# midi-switcher-smt-relay.net
KiCad netlist of a schematic drawn in EAGLE
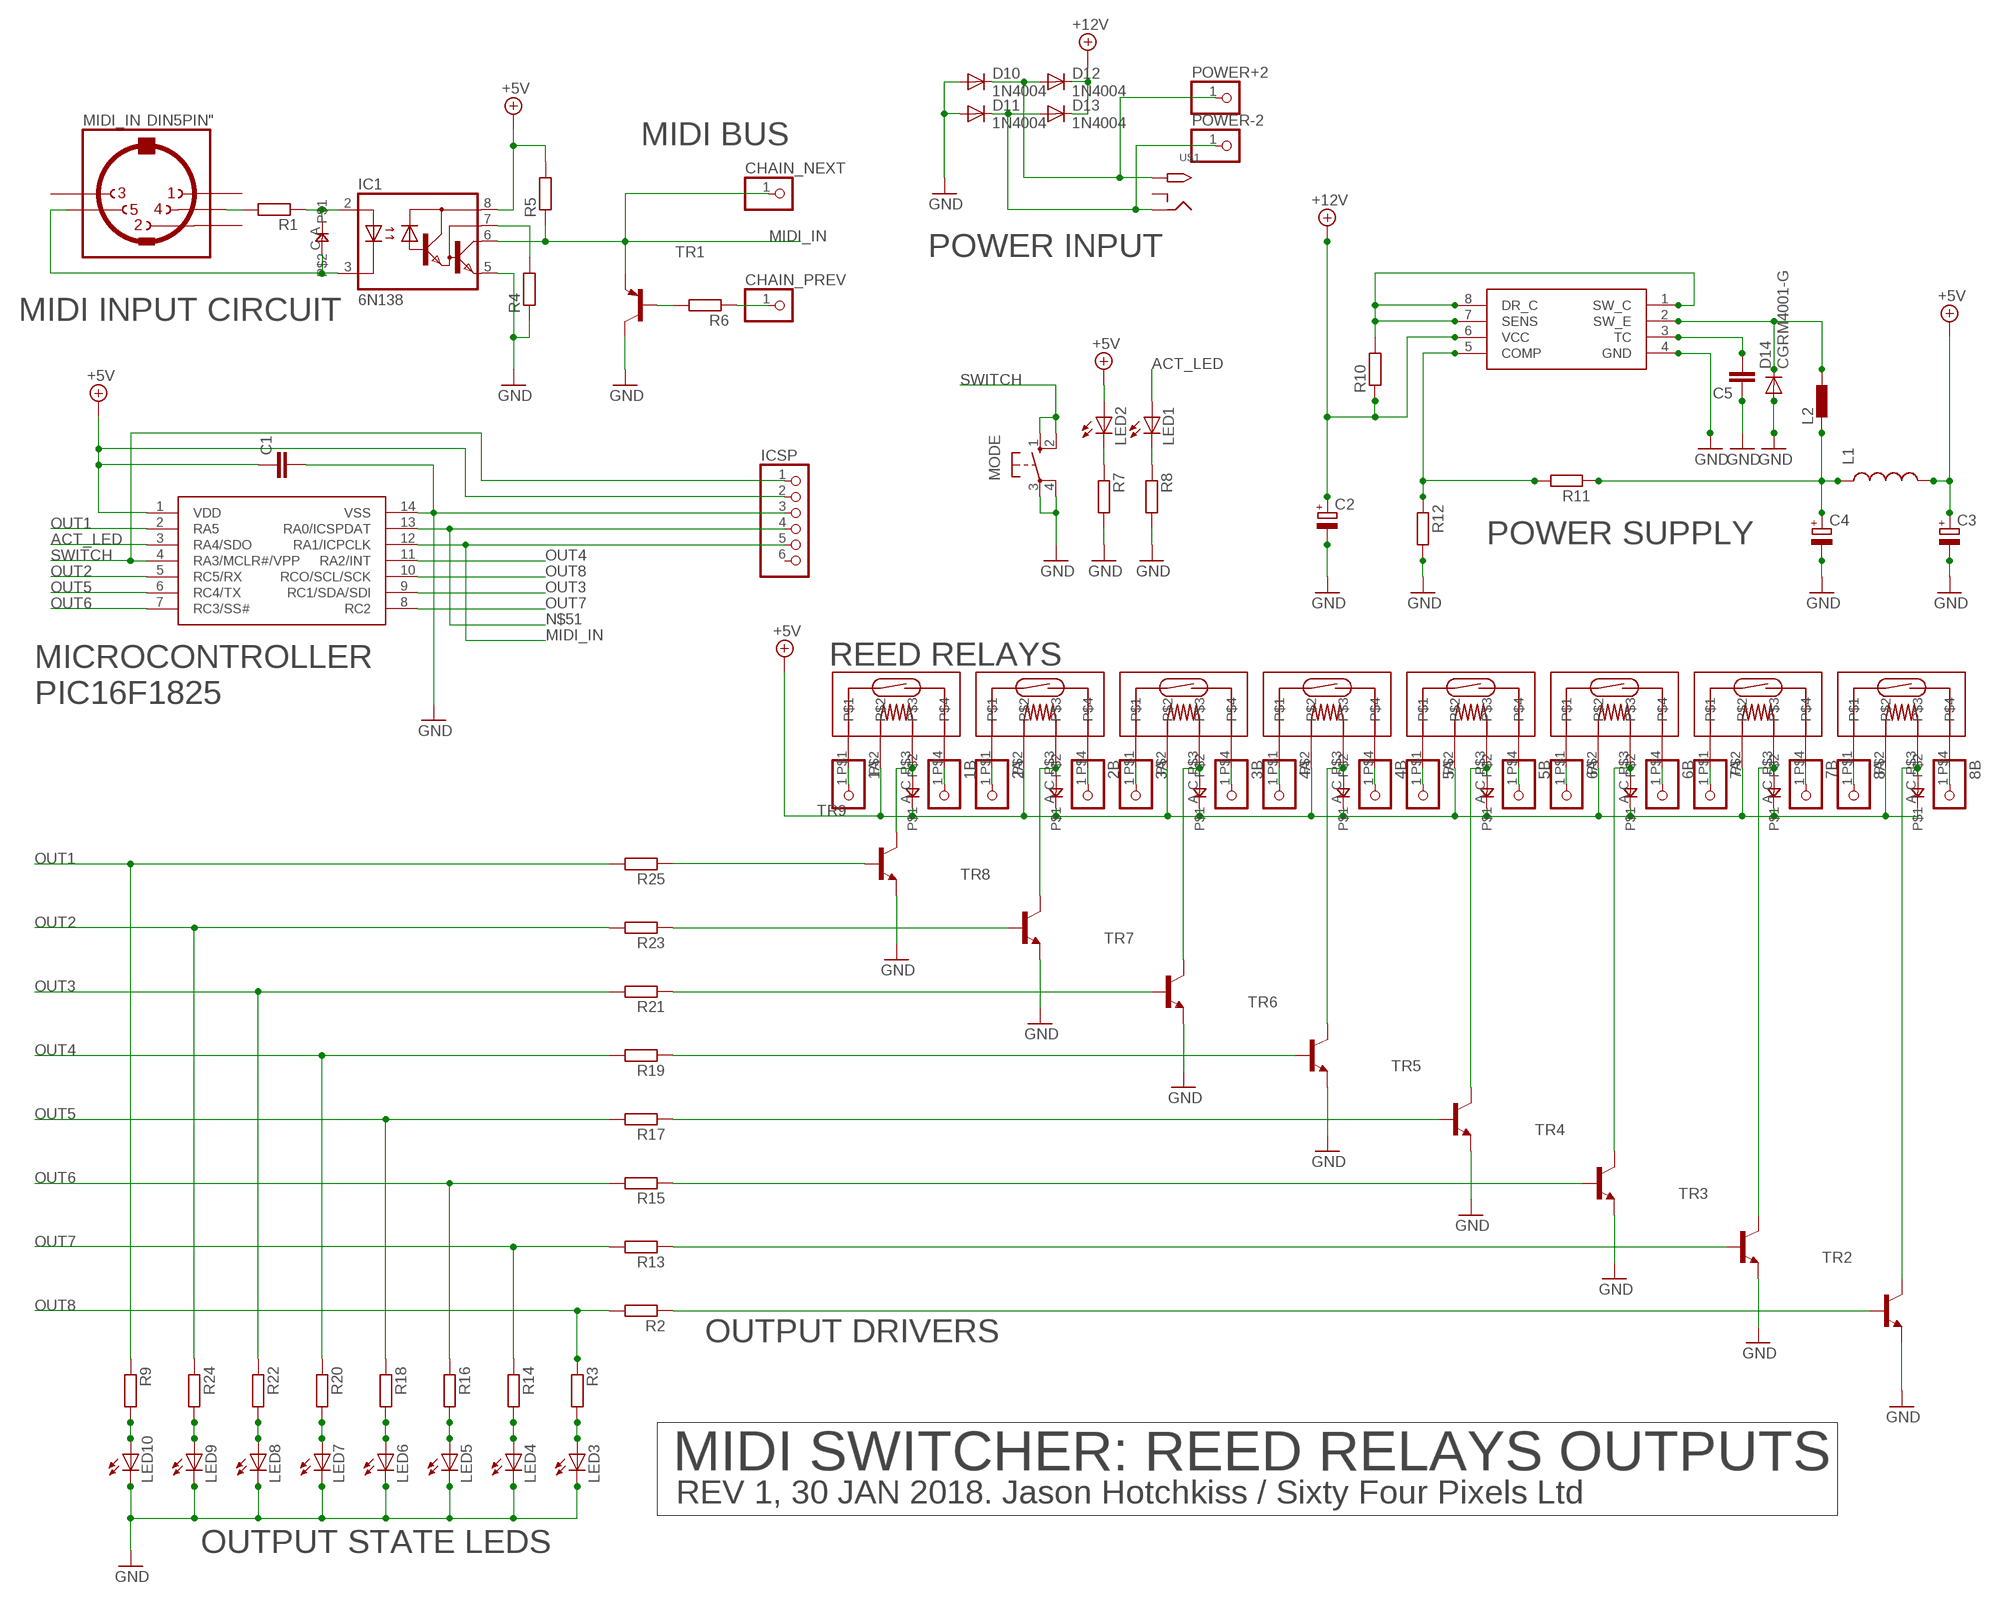
[diagram p0: schematic, sheet 1]

(export (version "E")
  (design (tool "Eeschema 10.0.6"))
  (components
    (comp (ref "1A")
      (value "PINHD-1X1")
      (footprint "eagle-import:1X01")
      (libsource (lib "eagle-import") (part "PINHD-1X1"))
    )
    (comp (ref "1B")
      (value "PINHD-1X1")
      (footprint "eagle-import:1X01")
      (libsource (lib "eagle-import") (part "PINHD-1X1"))
    )
    (comp (ref "2A")
      (value "PINHD-1X1")
      (footprint "eagle-import:1X01")
      (libsource (lib "eagle-import") (part "PINHD-1X1"))
    )
    (comp (ref "2B")
      (value "PINHD-1X1")
      (footprint "eagle-import:1X01")
      (libsource (lib "eagle-import") (part "PINHD-1X1"))
    )
    (comp (ref "3A")
      (value "PINHD-1X1")
      (footprint "eagle-import:1X01")
      (libsource (lib "eagle-import") (part "PINHD-1X1"))
    )
    (comp (ref "3B")
      (value "PINHD-1X1")
      (footprint "eagle-import:1X01")
      (libsource (lib "eagle-import") (part "PINHD-1X1"))
    )
    (comp (ref "4A")
      (value "PINHD-1X1")
      (footprint "eagle-import:1X01")
      (libsource (lib "eagle-import") (part "PINHD-1X1"))
    )
    (comp (ref "4B")
      (value "PINHD-1X1")
      (footprint "eagle-import:1X01")
      (libsource (lib "eagle-import") (part "PINHD-1X1"))
    )
    (comp (ref "5A")
      (value "PINHD-1X1")
      (footprint "eagle-import:1X01")
      (libsource (lib "eagle-import") (part "PINHD-1X1"))
    )
    (comp (ref "5B")
      (value "PINHD-1X1")
      (footprint "eagle-import:1X01")
      (libsource (lib "eagle-import") (part "PINHD-1X1"))
    )
    (comp (ref "6A")
      (value "PINHD-1X1")
      (footprint "eagle-import:1X01")
      (libsource (lib "eagle-import") (part "PINHD-1X1"))
    )
    (comp (ref "6B")
      (value "PINHD-1X1")
      (footprint "eagle-import:1X01")
      (libsource (lib "eagle-import") (part "PINHD-1X1"))
    )
    (comp (ref "7A")
      (value "PINHD-1X1")
      (footprint "eagle-import:1X01")
      (libsource (lib "eagle-import") (part "PINHD-1X1"))
    )
    (comp (ref "7B")
      (value "PINHD-1X1")
      (footprint "eagle-import:1X01")
      (libsource (lib "eagle-import") (part "PINHD-1X1"))
    )
    (comp (ref "8A")
      (value "PINHD-1X1")
      (footprint "eagle-import:1X01")
      (libsource (lib "eagle-import") (part "PINHD-1X1"))
    )
    (comp (ref "8B")
      (value "PINHD-1X1")
      (footprint "eagle-import:1X01")
      (libsource (lib "eagle-import") (part "PINHD-1X1"))
    )
    (comp (ref "C1")
      (value "C-EUC0805")
      (footprint "eagle-import:C0805")
      (libsource (lib "eagle-import") (part "C-EUC0805"))
    )
    (comp (ref "C2")
      (value "CPOL-EUE2.5-7")
      (footprint "eagle-import:E2,5-7")
      (libsource (lib "eagle-import") (part "CPOL-EUE2.5-7"))
    )
    (comp (ref "C3")
      (value "CPOL-EUE2.5-7")
      (footprint "eagle-import:E2,5-7")
      (libsource (lib "eagle-import") (part "CPOL-EUE2.5-7"))
    )
    (comp (ref "C4")
      (value "CPOL-EUE2.5-7")
      (footprint "eagle-import:E2,5-7")
      (libsource (lib "eagle-import") (part "CPOL-EUE2.5-7"))
    )
    (comp (ref "C5")
      (value "C-EUC0805")
      (footprint "eagle-import:C0805")
      (libsource (lib "eagle-import") (part "C-EUC0805"))
    )
    (comp (ref "CHAIN_NEXT")
      (value "PINHD-1X1")
      (footprint "eagle-import:1X01")
      (libsource (lib "eagle-import") (part "PINHD-1X1"))
    )
    (comp (ref "CHAIN_PREV")
      (value "PINHD-1X1")
      (footprint "eagle-import:1X01")
      (libsource (lib "eagle-import") (part "PINHD-1X1"))
    )
    (comp (ref "D1")
      (value "0805DIODE")
      (footprint "eagle-import:0805DIODE")
      (libsource (lib "eagle-import") (part "0805DIODE"))
    )
    (comp (ref "D2")
      (value "0805DIODE")
      (footprint "eagle-import:0805DIODE")
      (libsource (lib "eagle-import") (part "0805DIODE"))
    )
    (comp (ref "D3")
      (value "0805DIODE")
      (footprint "eagle-import:0805DIODE")
      (libsource (lib "eagle-import") (part "0805DIODE"))
    )
    (comp (ref "D4")
      (value "0805DIODE")
      (footprint "eagle-import:0805DIODE")
      (libsource (lib "eagle-import") (part "0805DIODE"))
    )
    (comp (ref "D5")
      (value "0805DIODE")
      (footprint "eagle-import:0805DIODE")
      (libsource (lib "eagle-import") (part "0805DIODE"))
    )
    (comp (ref "D6")
      (value "0805DIODE")
      (footprint "eagle-import:0805DIODE")
      (libsource (lib "eagle-import") (part "0805DIODE"))
    )
    (comp (ref "D7")
      (value "0805DIODE")
      (footprint "eagle-import:0805DIODE")
      (libsource (lib "eagle-import") (part "0805DIODE"))
    )
    (comp (ref "D8")
      (value "0805DIODE")
      (footprint "eagle-import:0805DIODE")
      (libsource (lib "eagle-import") (part "0805DIODE"))
    )
    (comp (ref "D9")
      (value "0805DIODE")
      (footprint "eagle-import:0805DIODE")
      (libsource (lib "eagle-import") (part "0805DIODE"))
    )
    (comp (ref "D10")
      (value "1N4004")
      (footprint "eagle-import:DO-VERT")
      (libsource (lib "eagle-import") (part "1N4004"))
    )
    (comp (ref "D11")
      (value "1N4004")
      (footprint "eagle-import:DO-VERT")
      (libsource (lib "eagle-import") (part "1N4004"))
    )
    (comp (ref "D12")
      (value "1N4004")
      (footprint "eagle-import:DO-VERT")
      (libsource (lib "eagle-import") (part "1N4004"))
    )
    (comp (ref "D13")
      (value "1N4004")
      (footprint "eagle-import:DO-VERT")
      (libsource (lib "eagle-import") (part "1N4004"))
    )
    (comp (ref "D14")
      (value "CGRM4001-G")
      (footprint "eagle-import:SOD-123_MINI-SMA")
      (libsource (lib "eagle-import") (part "CGRM400-G1"))
    )
    (comp (ref "IC1")
      (value "6N138")
      (footprint "eagle-import:DIL08")
      (libsource (lib "eagle-import") (part "6N138"))
    )
    (comp (ref "IC2")
      (value "PIC16F1825SO14")
      (footprint "eagle-import:SO14")
      (libsource (lib "eagle-import") (part "PIC16F1825SO14"))
    )
    (comp (ref "IC3")
      (value "SP34063A_BOOST_REG")
      (footprint "eagle-import:SOIC8")
      (libsource (lib "eagle-import") (part "SP34063A_BOOST_REG"))
    )
    (comp (ref "ICSP")
      (value "HEADER-1X6")
      (footprint "eagle-import:1X06_OVAL")
      (libsource (lib "eagle-import") (part "HEADER-1X6"))
    )
    (comp (ref "L1")
      (value "INDUCTOR1210")
      (footprint "eagle-import:1210")
      (libsource (lib "eagle-import") (part "INDUCTOR1210"))
    )
    (comp (ref "L2")
      (value "DR1030")
      (footprint "eagle-import:DR1030")
      (libsource (lib "eagle-import") (part "DR1030"))
    )
    (comp (ref "LED1")
      (value "LEDCHIP-LED0805")
      (footprint "eagle-import:CHIP-LED0805")
      (libsource (lib "eagle-import") (part "LEDCHIP-LED0805"))
    )
    (comp (ref "LED2")
      (value "LEDCHIP-LED0805")
      (footprint "eagle-import:CHIP-LED0805")
      (libsource (lib "eagle-import") (part "LEDCHIP-LED0805"))
    )
    (comp (ref "LED3")
      (value "LEDCHIP-LED0805")
      (footprint "eagle-import:CHIP-LED0805")
      (libsource (lib "eagle-import") (part "LEDCHIP-LED0805"))
    )
    (comp (ref "LED4")
      (value "LEDCHIP-LED0805")
      (footprint "eagle-import:CHIP-LED0805")
      (libsource (lib "eagle-import") (part "LEDCHIP-LED0805"))
    )
    (comp (ref "LED5")
      (value "LEDCHIP-LED0805")
      (footprint "eagle-import:CHIP-LED0805")
      (libsource (lib "eagle-import") (part "LEDCHIP-LED0805"))
    )
    (comp (ref "LED6")
      (value "LEDCHIP-LED0805")
      (footprint "eagle-import:CHIP-LED0805")
      (libsource (lib "eagle-import") (part "LEDCHIP-LED0805"))
    )
    (comp (ref "LED7")
      (value "LEDCHIP-LED0805")
      (footprint "eagle-import:CHIP-LED0805")
      (libsource (lib "eagle-import") (part "LEDCHIP-LED0805"))
    )
    (comp (ref "LED8")
      (value "LEDCHIP-LED0805")
      (footprint "eagle-import:CHIP-LED0805")
      (libsource (lib "eagle-import") (part "LEDCHIP-LED0805"))
    )
    (comp (ref "LED9")
      (value "LEDCHIP-LED0805")
      (footprint "eagle-import:CHIP-LED0805")
      (libsource (lib "eagle-import") (part "LEDCHIP-LED0805"))
    )
    (comp (ref "LED10")
      (value "LEDCHIP-LED0805")
      (footprint "eagle-import:CHIP-LED0805")
      (libsource (lib "eagle-import") (part "LEDCHIP-LED0805"))
    )
    (comp (ref "MIDI_IN")
      (value "DIN5PIN\"")
      (footprint "eagle-import:TRUCONN90")
      (libsource (lib "eagle-import") (part "DIN5PIN{dblquote}"))
    )
    (comp (ref "MODE")
      (value "10-XX")
      (footprint "eagle-import:B3F-10XX")
      (libsource (lib "eagle-import") (part "10-XX"))
    )
    (comp (ref "POWER+2")
      (value "PINHD-1X1")
      (footprint "eagle-import:1X01")
      (libsource (lib "eagle-import") (part "PINHD-1X1"))
    )
    (comp (ref "POWER-2")
      (value "PINHD-1X1")
      (footprint "eagle-import:1X01")
      (libsource (lib "eagle-import") (part "PINHD-1X1"))
    )
    (comp (ref "R1")
      (value "R-EU_R0805")
      (footprint "eagle-import:R0805")
      (libsource (lib "eagle-import") (part "R-EU_R0805"))
    )
    (comp (ref "R2")
      (value "R-EU_R0805")
      (footprint "eagle-import:R0805")
      (libsource (lib "eagle-import") (part "R-EU_R0805"))
    )
    (comp (ref "R3")
      (value "R-EU_R0805")
      (footprint "eagle-import:R0805")
      (libsource (lib "eagle-import") (part "R-EU_R0805"))
    )
    (comp (ref "R4")
      (value "R-EU_R0805")
      (footprint "eagle-import:R0805")
      (libsource (lib "eagle-import") (part "R-EU_R0805"))
    )
    (comp (ref "R5")
      (value "R-EU_R0805")
      (footprint "eagle-import:R0805")
      (libsource (lib "eagle-import") (part "R-EU_R0805"))
    )
    (comp (ref "R6")
      (value "R-EU_R0805")
      (footprint "eagle-import:R0805")
      (libsource (lib "eagle-import") (part "R-EU_R0805"))
    )
    (comp (ref "R7")
      (value "R-EU_R0805")
      (footprint "eagle-import:R0805")
      (libsource (lib "eagle-import") (part "R-EU_R0805"))
    )
    (comp (ref "R8")
      (value "R-EU_R0805")
      (footprint "eagle-import:R0805")
      (libsource (lib "eagle-import") (part "R-EU_R0805"))
    )
    (comp (ref "R9")
      (value "R-EU_R0805")
      (footprint "eagle-import:R0805")
      (libsource (lib "eagle-import") (part "R-EU_R0805"))
    )
    (comp (ref "R10")
      (value "R-EU_R0805")
      (footprint "eagle-import:R0805")
      (libsource (lib "eagle-import") (part "R-EU_R0805"))
    )
    (comp (ref "R11")
      (value "R-EU_R0805")
      (footprint "eagle-import:R0805")
      (libsource (lib "eagle-import") (part "R-EU_R0805"))
    )
    (comp (ref "R12")
      (value "R-EU_R0805")
      (footprint "eagle-import:R0805")
      (libsource (lib "eagle-import") (part "R-EU_R0805"))
    )
    (comp (ref "R13")
      (value "R-EU_R0805")
      (footprint "eagle-import:R0805")
      (libsource (lib "eagle-import") (part "R-EU_R0805"))
    )
    (comp (ref "R14")
      (value "R-EU_R0805")
      (footprint "eagle-import:R0805")
      (libsource (lib "eagle-import") (part "R-EU_R0805"))
    )
    (comp (ref "R15")
      (value "R-EU_R0805")
      (footprint "eagle-import:R0805")
      (libsource (lib "eagle-import") (part "R-EU_R0805"))
    )
    (comp (ref "R16")
      (value "R-EU_R0805")
      (footprint "eagle-import:R0805")
      (libsource (lib "eagle-import") (part "R-EU_R0805"))
    )
    (comp (ref "R17")
      (value "R-EU_R0805")
      (footprint "eagle-import:R0805")
      (libsource (lib "eagle-import") (part "R-EU_R0805"))
    )
    (comp (ref "R18")
      (value "R-EU_R0805")
      (footprint "eagle-import:R0805")
      (libsource (lib "eagle-import") (part "R-EU_R0805"))
    )
    (comp (ref "R19")
      (value "R-EU_R0805")
      (footprint "eagle-import:R0805")
      (libsource (lib "eagle-import") (part "R-EU_R0805"))
    )
    (comp (ref "R20")
      (value "R-EU_R0805")
      (footprint "eagle-import:R0805")
      (libsource (lib "eagle-import") (part "R-EU_R0805"))
    )
    (comp (ref "R21")
      (value "R-EU_R0805")
      (footprint "eagle-import:R0805")
      (libsource (lib "eagle-import") (part "R-EU_R0805"))
    )
    (comp (ref "R22")
      (value "R-EU_R0805")
      (footprint "eagle-import:R0805")
      (libsource (lib "eagle-import") (part "R-EU_R0805"))
    )
    (comp (ref "R23")
      (value "R-EU_R0805")
      (footprint "eagle-import:R0805")
      (libsource (lib "eagle-import") (part "R-EU_R0805"))
    )
    (comp (ref "R24")
      (value "R-EU_R0805")
      (footprint "eagle-import:R0805")
      (libsource (lib "eagle-import") (part "R-EU_R0805"))
    )
    (comp (ref "R25")
      (value "R-EU_R0805")
      (footprint "eagle-import:R0805")
      (libsource (lib "eagle-import") (part "R-EU_R0805"))
    )
    (comp (ref "RL1")
      (value "9007-REED-RELAY")
      (footprint "eagle-import:9007-REED-RELAY")
      (libsource (lib "eagle-import") (part "9007-REED-RELAY"))
    )
    (comp (ref "RL2")
      (value "9007-REED-RELAY")
      (footprint "eagle-import:9007-REED-RELAY")
      (libsource (lib "eagle-import") (part "9007-REED-RELAY"))
    )
    (comp (ref "RL3")
      (value "9007-REED-RELAY")
      (footprint "eagle-import:9007-REED-RELAY")
      (libsource (lib "eagle-import") (part "9007-REED-RELAY"))
    )
    (comp (ref "RL4")
      (value "9007-REED-RELAY")
      (footprint "eagle-import:9007-REED-RELAY")
      (libsource (lib "eagle-import") (part "9007-REED-RELAY"))
    )
    (comp (ref "RL5")
      (value "9007-REED-RELAY")
      (footprint "eagle-import:9007-REED-RELAY")
      (libsource (lib "eagle-import") (part "9007-REED-RELAY"))
    )
    (comp (ref "RL6")
      (value "9007-REED-RELAY")
      (footprint "eagle-import:9007-REED-RELAY")
      (libsource (lib "eagle-import") (part "9007-REED-RELAY"))
    )
    (comp (ref "RL7")
      (value "9007-REED-RELAY")
      (footprint "eagle-import:9007-REED-RELAY")
      (libsource (lib "eagle-import") (part "9007-REED-RELAY"))
    )
    (comp (ref "RL8")
      (value "9007-REED-RELAY")
      (footprint "eagle-import:9007-REED-RELAY")
      (libsource (lib "eagle-import") (part "9007-REED-RELAY"))
    )
    (comp (ref "TR1")
      (value "MMBT3906LT1-PNP-SOT23-BEC")
      (footprint "eagle-import:SOT23-BEC")
      (libsource (lib "eagle-import") (part "-PNP-SOT23-BECMMBT3906LT1"))
    )
    (comp (ref "TR2")
      (value "MMBT3904LT1-NPN-SOT23-BEC")
      (footprint "eagle-import:SOT23-BEC")
      (libsource (lib "eagle-import") (part "-NPN-SOT23-BECMMBT3904LT1"))
    )
    (comp (ref "TR3")
      (value "MMBT3904LT1-NPN-SOT23-BEC")
      (footprint "eagle-import:SOT23-BEC")
      (libsource (lib "eagle-import") (part "-NPN-SOT23-BECMMBT3904LT1"))
    )
    (comp (ref "TR4")
      (value "MMBT3904LT1-NPN-SOT23-BEC")
      (footprint "eagle-import:SOT23-BEC")
      (libsource (lib "eagle-import") (part "-NPN-SOT23-BECMMBT3904LT1"))
    )
    (comp (ref "TR5")
      (value "MMBT3904LT1-NPN-SOT23-BEC")
      (footprint "eagle-import:SOT23-BEC")
      (libsource (lib "eagle-import") (part "-NPN-SOT23-BECMMBT3904LT1"))
    )
    (comp (ref "TR6")
      (value "MMBT3904LT1-NPN-SOT23-BEC")
      (footprint "eagle-import:SOT23-BEC")
      (libsource (lib "eagle-import") (part "-NPN-SOT23-BECMMBT3904LT1"))
    )
    (comp (ref "TR7")
      (value "MMBT3904LT1-NPN-SOT23-BEC")
      (footprint "eagle-import:SOT23-BEC")
      (libsource (lib "eagle-import") (part "-NPN-SOT23-BECMMBT3904LT1"))
    )
    (comp (ref "TR8")
      (value "MMBT3904LT1-NPN-SOT23-BEC")
      (footprint "eagle-import:SOT23-BEC")
      (libsource (lib "eagle-import") (part "-NPN-SOT23-BECMMBT3904LT1"))
    )
    (comp (ref "TR9")
      (value "MMBT3904LT1-NPN-SOT23-BEC")
      (footprint "eagle-import:SOT23-BEC")
      (libsource (lib "eagle-import") (part "-NPN-SOT23-BECMMBT3904LT1"))
    )
    (comp (ref "U$1")
      (value "2.1MMJACKTHM")
      (footprint "eagle-import:PJ-102A")
      (libsource (lib "eagle-import") (part "2.1MMJACKTHM"))
    )
  )
  (nets
    (net (code "1") (name "+5V") (class "Default")
      (node (ref "C1") (pin "1") (pinfunction "1_1") (pintype "passive"))
      (node (ref "C3") (pin "+") (pinfunction "+_+") (pintype "passive"))
      (node (ref "D2") (pin "A") (pinfunction "P$2_A") (pintype "bidirectional"))
      (node (ref "D3") (pin "A") (pinfunction "P$2_A") (pintype "bidirectional"))
      (node (ref "D4") (pin "A") (pinfunction "P$2_A") (pintype "bidirectional"))
      (node (ref "D5") (pin "A") (pinfunction "P$2_A") (pintype "bidirectional"))
      (node (ref "D6") (pin "A") (pinfunction "P$2_A") (pintype "bidirectional"))
      (node (ref "D7") (pin "A") (pinfunction "P$2_A") (pintype "bidirectional"))
      (node (ref "D8") (pin "A") (pinfunction "P$2_A") (pintype "bidirectional"))
      (node (ref "D9") (pin "A") (pinfunction "P$2_A") (pintype "bidirectional"))
      (node (ref "IC1") (pin "8") (pinfunction "VCC_8") (pintype "passive"))
      (node (ref "IC2") (pin "1") (pinfunction "VDD_1") (pintype "power_in"))
      (node (ref "ICSP") (pin "2") (pinfunction "2_2") (pintype "passive"))
      (node (ref "L1") (pin "2") (pinfunction "2_2") (pintype "passive"))
      (node (ref "LED2") (pin "A") (pinfunction "A_A") (pintype "passive"))
      (node (ref "R5") (pin "2") (pinfunction "2_2") (pintype "passive"))
      (node (ref "RL1") (pin "P$2") (pinfunction "P$2_P$2") (pintype "bidirectional"))
      (node (ref "RL2") (pin "P$2") (pinfunction "P$2_P$2") (pintype "bidirectional"))
      (node (ref "RL3") (pin "P$2") (pinfunction "P$2_P$2") (pintype "bidirectional"))
      (node (ref "RL4") (pin "P$2") (pinfunction "P$2_P$2") (pintype "bidirectional"))
      (node (ref "RL5") (pin "P$2") (pinfunction "P$2_P$2") (pintype "bidirectional"))
      (node (ref "RL6") (pin "P$2") (pinfunction "P$2_P$2") (pintype "bidirectional"))
      (node (ref "RL7") (pin "P$2") (pinfunction "P$2_P$2") (pintype "bidirectional"))
      (node (ref "RL8") (pin "P$2") (pinfunction "P$2_P$2") (pintype "bidirectional"))
    )
    (net (code "2") (name "+12V") (class "Default")
      (node (ref "C2") (pin "+") (pinfunction "+_+") (pintype "passive"))
      (node (ref "D12") (pin "C") (pinfunction "C_C") (pintype "passive"))
      (node (ref "D13") (pin "C") (pinfunction "C_C") (pintype "passive"))
      (node (ref "IC3") (pin "6") (pinfunction "VCC_6") (pintype "bidirectional"))
      (node (ref "R10") (pin "1") (pinfunction "1_1") (pintype "passive"))
    )
    (net (code "3") (name "/ACT_LED") (class "Default")
      (node (ref "IC2") (pin "3") (pinfunction "RA4/SDO_3") (pintype "bidirectional"))
      (node (ref "LED1") (pin "A") (pinfunction "A_A") (pintype "passive"))
    )
    (net (code "4") (name "/MIDI_IN") (class "Default")
      (node (ref "CHAIN_NEXT") (pin "1") (pinfunction "1_1") (pintype "passive"))
      (node (ref "IC1") (pin "6") (pinfunction "VO_6") (pintype "passive"))
      (node (ref "IC2") (pin "12") (pinfunction "RA1/ICPCLK_12") (pintype "bidirectional"))
      (node (ref "ICSP") (pin "5") (pinfunction "5_5") (pintype "passive"))
      (node (ref "R5") (pin "1") (pinfunction "1_1") (pintype "passive"))
      (node (ref "TR1") (pin "E") (pinfunction "E_E") (pintype "passive"))
    )
    (net (code "5") (name "/N$51") (class "Default")
      (node (ref "IC2") (pin "13") (pinfunction "RA0/ICSPDAT_13") (pintype "bidirectional"))
      (node (ref "ICSP") (pin "4") (pinfunction "4_4") (pintype "passive"))
    )
    (net (code "6") (name "/OUT1") (class "Default")
      (node (ref "IC2") (pin "2") (pinfunction "RA5_2") (pintype "bidirectional"))
      (node (ref "R25") (pin "2") (pinfunction "2_2") (pintype "passive"))
      (node (ref "R9") (pin "1") (pinfunction "1_1") (pintype "passive"))
    )
    (net (code "7") (name "/OUT2") (class "Default")
      (node (ref "IC2") (pin "5") (pinfunction "RC5/RX_5") (pintype "bidirectional"))
      (node (ref "R23") (pin "2") (pinfunction "2_2") (pintype "passive"))
      (node (ref "R24") (pin "1") (pinfunction "1_1") (pintype "passive"))
    )
    (net (code "8") (name "/OUT3") (class "Default")
      (node (ref "IC2") (pin "9") (pinfunction "RC1/SDA/SDI_9") (pintype "bidirectional"))
      (node (ref "R21") (pin "2") (pinfunction "2_2") (pintype "passive"))
      (node (ref "R22") (pin "1") (pinfunction "1_1") (pintype "passive"))
    )
    (net (code "9") (name "/OUT4") (class "Default")
      (node (ref "IC2") (pin "11") (pinfunction "RA2/INT_11") (pintype "bidirectional"))
      (node (ref "R19") (pin "2") (pinfunction "2_2") (pintype "passive"))
      (node (ref "R20") (pin "1") (pinfunction "1_1") (pintype "passive"))
    )
    (net (code "10") (name "/OUT5") (class "Default")
      (node (ref "IC2") (pin "6") (pinfunction "RC4/TX_6") (pintype "bidirectional"))
      (node (ref "R17") (pin "2") (pinfunction "2_2") (pintype "passive"))
      (node (ref "R18") (pin "1") (pinfunction "1_1") (pintype "passive"))
    )
    (net (code "11") (name "/OUT6") (class "Default")
      (node (ref "IC2") (pin "7") (pinfunction "RC3/SS#_7") (pintype "bidirectional"))
      (node (ref "R15") (pin "2") (pinfunction "2_2") (pintype "passive"))
      (node (ref "R16") (pin "1") (pinfunction "1_1") (pintype "passive"))
    )
    (net (code "12") (name "/OUT7") (class "Default")
      (node (ref "IC2") (pin "8") (pinfunction "RC2_8") (pintype "bidirectional"))
      (node (ref "R13") (pin "2") (pinfunction "2_2") (pintype "passive"))
      (node (ref "R14") (pin "1") (pinfunction "1_1") (pintype "passive"))
    )
    (net (code "13") (name "/OUT8") (class "Default")
      (node (ref "IC2") (pin "10") (pinfunction "RCO/SCL/SCK_10") (pintype "bidirectional"))
      (node (ref "R2") (pin "2") (pinfunction "2_2") (pintype "passive"))
      (node (ref "R3") (pin "1") (pinfunction "1_1") (pintype "passive"))
    )
    (net (code "14") (name "/SWITCH") (class "Default")
      (node (ref "IC2") (pin "4") (pinfunction "RA3/MCLR#/VPP_4") (pintype "input"))
      (node (ref "ICSP") (pin "1") (pinfunction "1_1") (pintype "passive"))
      (node (ref "MODE") (pin "1") (pinfunction "S_1") (pintype "passive"))
      (node (ref "MODE") (pin "2") (pinfunction "S1_2") (pintype "passive"))
    )
    (net (code "15") (name "GND") (class "Default")
      (node (ref "C1") (pin "2") (pinfunction "2_2") (pintype "passive"))
      (node (ref "C2") (pin "-") (pinfunction "-_-") (pintype "passive"))
      (node (ref "C3") (pin "-") (pinfunction "-_-") (pintype "passive"))
      (node (ref "C4") (pin "-") (pinfunction "-_-") (pintype "passive"))
      (node (ref "C5") (pin "1") (pinfunction "1_1") (pintype "passive"))
      (node (ref "D10") (pin "A") (pinfunction "A_A") (pintype "passive"))
      (node (ref "D11") (pin "A") (pinfunction "A_A") (pintype "passive"))
      (node (ref "D14") (pin "A") (pinfunction "A_A") (pintype "passive"))
      (node (ref "IC1") (pin "5") (pinfunction "GND_5") (pintype "passive"))
      (node (ref "IC2") (pin "14") (pinfunction "VSS_14") (pintype "power_in"))
      (node (ref "IC3") (pin "4") (pinfunction "GND_4") (pintype "bidirectional"))
      (node (ref "ICSP") (pin "3") (pinfunction "3_3") (pintype "passive"))
      (node (ref "LED10") (pin "C") (pinfunction "C_C") (pintype "passive"))
      (node (ref "LED3") (pin "C") (pinfunction "C_C") (pintype "passive"))
      (node (ref "LED4") (pin "C") (pinfunction "C_C") (pintype "passive"))
      (node (ref "LED5") (pin "C") (pinfunction "C_C") (pintype "passive"))
      (node (ref "LED6") (pin "C") (pinfunction "C_C") (pintype "passive"))
      (node (ref "LED7") (pin "C") (pinfunction "C_C") (pintype "passive"))
      (node (ref "LED8") (pin "C") (pinfunction "C_C") (pintype "passive"))
      (node (ref "LED9") (pin "C") (pinfunction "C_C") (pintype "passive"))
      (node (ref "MODE") (pin "3") (pinfunction "P_3") (pintype "passive"))
      (node (ref "MODE") (pin "4") (pinfunction "P1_4") (pintype "passive"))
      (node (ref "R12") (pin "2") (pinfunction "2_2") (pintype "passive"))
      (node (ref "R4") (pin "1") (pinfunction "1_1") (pintype "passive"))
      (node (ref "R7") (pin "2") (pinfunction "2_2") (pintype "passive"))
      (node (ref "R8") (pin "2") (pinfunction "2_2") (pintype "passive"))
      (node (ref "TR1") (pin "C") (pinfunction "C_C") (pintype "passive"))
      (node (ref "TR2") (pin "E") (pinfunction "E_E") (pintype "passive"))
      (node (ref "TR3") (pin "E") (pinfunction "E_E") (pintype "passive"))
      (node (ref "TR4") (pin "E") (pinfunction "E_E") (pintype "passive"))
      (node (ref "TR5") (pin "E") (pinfunction "E_E") (pintype "passive"))
      (node (ref "TR6") (pin "E") (pinfunction "E_E") (pintype "passive"))
      (node (ref "TR7") (pin "E") (pinfunction "E_E") (pintype "passive"))
      (node (ref "TR8") (pin "E") (pinfunction "E_E") (pintype "passive"))
      (node (ref "TR9") (pin "E") (pinfunction "E_E") (pintype "passive"))
    )
    (net (code "16") (name "Net-(1A-Pad1)") (class "Default")
      (node (ref "1A") (pin "1") (pinfunction "1_1") (pintype "passive"))
      (node (ref "RL8") (pin "P$1") (pinfunction "P$1_P$1") (pintype "bidirectional"))
    )
    (net (code "17") (name "Net-(1B-Pad1)") (class "Default")
      (node (ref "1B") (pin "1") (pinfunction "1_1") (pintype "passive"))
      (node (ref "RL8") (pin "P$4") (pinfunction "P$4_P$4") (pintype "bidirectional"))
    )
    (net (code "18") (name "Net-(2A-Pad1)") (class "Default")
      (node (ref "2A") (pin "1") (pinfunction "1_1") (pintype "passive"))
      (node (ref "RL7") (pin "P$1") (pinfunction "P$1_P$1") (pintype "bidirectional"))
    )
    (net (code "19") (name "Net-(2B-Pad1)") (class "Default")
      (node (ref "2B") (pin "1") (pinfunction "1_1") (pintype "passive"))
      (node (ref "RL7") (pin "P$4") (pinfunction "P$4_P$4") (pintype "bidirectional"))
    )
    (net (code "20") (name "Net-(3A-Pad1)") (class "Default")
      (node (ref "3A") (pin "1") (pinfunction "1_1") (pintype "passive"))
      (node (ref "RL6") (pin "P$1") (pinfunction "P$1_P$1") (pintype "bidirectional"))
    )
    (net (code "21") (name "Net-(3B-Pad1)") (class "Default")
      (node (ref "3B") (pin "1") (pinfunction "1_1") (pintype "passive"))
      (node (ref "RL6") (pin "P$4") (pinfunction "P$4_P$4") (pintype "bidirectional"))
    )
    (net (code "22") (name "Net-(4A-Pad1)") (class "Default")
      (node (ref "4A") (pin "1") (pinfunction "1_1") (pintype "passive"))
      (node (ref "RL5") (pin "P$1") (pinfunction "P$1_P$1") (pintype "bidirectional"))
    )
    (net (code "23") (name "Net-(4B-Pad1)") (class "Default")
      (node (ref "4B") (pin "1") (pinfunction "1_1") (pintype "passive"))
      (node (ref "RL5") (pin "P$4") (pinfunction "P$4_P$4") (pintype "bidirectional"))
    )
    (net (code "24") (name "Net-(5A-Pad1)") (class "Default")
      (node (ref "5A") (pin "1") (pinfunction "1_1") (pintype "passive"))
      (node (ref "RL4") (pin "P$1") (pinfunction "P$1_P$1") (pintype "bidirectional"))
    )
    (net (code "25") (name "Net-(5B-Pad1)") (class "Default")
      (node (ref "5B") (pin "1") (pinfunction "1_1") (pintype "passive"))
      (node (ref "RL4") (pin "P$4") (pinfunction "P$4_P$4") (pintype "bidirectional"))
    )
    (net (code "26") (name "Net-(6A-Pad1)") (class "Default")
      (node (ref "6A") (pin "1") (pinfunction "1_1") (pintype "passive"))
      (node (ref "RL3") (pin "P$1") (pinfunction "P$1_P$1") (pintype "bidirectional"))
    )
    (net (code "27") (name "Net-(6B-Pad1)") (class "Default")
      (node (ref "6B") (pin "1") (pinfunction "1_1") (pintype "passive"))
      (node (ref "RL3") (pin "P$4") (pinfunction "P$4_P$4") (pintype "bidirectional"))
    )
    (net (code "28") (name "Net-(7A-Pad1)") (class "Default")
      (node (ref "7A") (pin "1") (pinfunction "1_1") (pintype "passive"))
      (node (ref "RL2") (pin "P$1") (pinfunction "P$1_P$1") (pintype "bidirectional"))
    )
    (net (code "29") (name "Net-(7B-Pad1)") (class "Default")
      (node (ref "7B") (pin "1") (pinfunction "1_1") (pintype "passive"))
      (node (ref "RL2") (pin "P$4") (pinfunction "P$4_P$4") (pintype "bidirectional"))
    )
    (net (code "30") (name "Net-(8A-Pad1)") (class "Default")
      (node (ref "8A") (pin "1") (pinfunction "1_1") (pintype "passive"))
      (node (ref "RL1") (pin "P$1") (pinfunction "P$1_P$1") (pintype "bidirectional"))
    )
    (net (code "31") (name "Net-(8B-Pad1)") (class "Default")
      (node (ref "8B") (pin "1") (pinfunction "1_1") (pintype "passive"))
      (node (ref "RL1") (pin "P$4") (pinfunction "P$4_P$4") (pintype "bidirectional"))
    )
    (net (code "32") (name "Net-(C4-Pad+)") (class "Default")
      (node (ref "C4") (pin "+") (pinfunction "+_+") (pintype "passive"))
      (node (ref "L1") (pin "1") (pinfunction "1_1") (pintype "passive"))
      (node (ref "L2") (pin "1") (pinfunction "1_1") (pintype "passive"))
      (node (ref "R11") (pin "1") (pinfunction "1_1") (pintype "passive"))
    )
    (net (code "33") (name "Net-(CHAIN_PREV-Pad1)") (class "Default")
      (node (ref "CHAIN_PREV") (pin "1") (pinfunction "1_1") (pintype "passive"))
      (node (ref "R6") (pin "1") (pinfunction "1_1") (pintype "passive"))
    )
    (net (code "34") (name "Net-(D1-P$1)") (class "Default")
      (node (ref "D1") (pin "C") (pinfunction "P$1_C") (pintype "bidirectional"))
      (node (ref "IC1") (pin "3") (pinfunction "C_3") (pintype "passive"))
      (node (ref "MIDI_IN") (pin "5") (pinfunction "5_5") (pintype "passive"))
    )
    (net (code "35") (name "Net-(D1-P$2)") (class "Default")
      (node (ref "D1") (pin "A") (pinfunction "P$2_A") (pintype "bidirectional"))
      (node (ref "IC1") (pin "2") (pinfunction "A_2") (pintype "passive"))
      (node (ref "R1") (pin "1") (pinfunction "1_1") (pintype "passive"))
    )
    (net (code "36") (name "Net-(D2-P$1)") (class "Default")
      (node (ref "D2") (pin "C") (pinfunction "P$1_C") (pintype "bidirectional"))
      (node (ref "RL1") (pin "P$3") (pinfunction "P$3_P$3") (pintype "bidirectional"))
      (node (ref "TR2") (pin "C") (pinfunction "C_C") (pintype "passive"))
    )
    (net (code "37") (name "Net-(D3-P$1)") (class "Default")
      (node (ref "D3") (pin "C") (pinfunction "P$1_C") (pintype "bidirectional"))
      (node (ref "RL2") (pin "P$3") (pinfunction "P$3_P$3") (pintype "bidirectional"))
      (node (ref "TR3") (pin "C") (pinfunction "C_C") (pintype "passive"))
    )
    (net (code "38") (name "Net-(D4-P$1)") (class "Default")
      (node (ref "D4") (pin "C") (pinfunction "P$1_C") (pintype "bidirectional"))
      (node (ref "RL3") (pin "P$3") (pinfunction "P$3_P$3") (pintype "bidirectional"))
      (node (ref "TR4") (pin "C") (pinfunction "C_C") (pintype "passive"))
    )
    (net (code "39") (name "Net-(D5-P$1)") (class "Default")
      (node (ref "D5") (pin "C") (pinfunction "P$1_C") (pintype "bidirectional"))
      (node (ref "RL4") (pin "P$3") (pinfunction "P$3_P$3") (pintype "bidirectional"))
      (node (ref "TR5") (pin "C") (pinfunction "C_C") (pintype "passive"))
    )
    (net (code "40") (name "Net-(D6-P$1)") (class "Default")
      (node (ref "D6") (pin "C") (pinfunction "P$1_C") (pintype "bidirectional"))
      (node (ref "RL5") (pin "P$3") (pinfunction "P$3_P$3") (pintype "bidirectional"))
      (node (ref "TR6") (pin "C") (pinfunction "C_C") (pintype "passive"))
    )
    (net (code "41") (name "Net-(D7-P$1)") (class "Default")
      (node (ref "D7") (pin "C") (pinfunction "P$1_C") (pintype "bidirectional"))
      (node (ref "RL6") (pin "P$3") (pinfunction "P$3_P$3") (pintype "bidirectional"))
      (node (ref "TR7") (pin "C") (pinfunction "C_C") (pintype "passive"))
    )
    (net (code "42") (name "Net-(D8-P$1)") (class "Default")
      (node (ref "D8") (pin "C") (pinfunction "P$1_C") (pintype "bidirectional"))
      (node (ref "RL7") (pin "P$3") (pinfunction "P$3_P$3") (pintype "bidirectional"))
      (node (ref "TR8") (pin "C") (pinfunction "C_C") (pintype "passive"))
    )
    (net (code "43") (name "Net-(D9-P$1)") (class "Default")
      (node (ref "D9") (pin "C") (pinfunction "P$1_C") (pintype "bidirectional"))
      (node (ref "RL8") (pin "P$3") (pinfunction "P$3_P$3") (pintype "bidirectional"))
      (node (ref "TR9") (pin "C") (pinfunction "C_C") (pintype "passive"))
    )
    (net (code "44") (name "Net-(D10-PadC)") (class "Default")
      (node (ref "D10") (pin "C") (pinfunction "C_C") (pintype "passive"))
      (node (ref "D12") (pin "A") (pinfunction "A_A") (pintype "passive"))
      (node (ref "POWER+2") (pin "1") (pinfunction "1_1") (pintype "passive"))
      (node (ref "U$1") (pin "TIP") (pinfunction "TIP_TIP") (pintype "bidirectional"))
    )
    (net (code "45") (name "Net-(D11-PadC)") (class "Default")
      (node (ref "D11") (pin "C") (pinfunction "C_C") (pintype "passive"))
      (node (ref "D13") (pin "A") (pinfunction "A_A") (pintype "passive"))
      (node (ref "POWER-2") (pin "1") (pinfunction "1_1") (pintype "passive"))
      (node (ref "U$1") (pin "RING") (pinfunction "RING_RING") (pintype "bidirectional"))
    )
    (net (code "46") (name "Net-(IC1-VB)") (class "Default")
      (node (ref "IC1") (pin "7") (pinfunction "VB_7") (pintype "passive"))
      (node (ref "R4") (pin "2") (pinfunction "2_2") (pintype "passive"))
    )
    (net (code "47") (name "Net-(IC3-COMP)") (class "Default")
      (node (ref "IC3") (pin "5") (pinfunction "COMP_5") (pintype "bidirectional"))
      (node (ref "R11") (pin "2") (pinfunction "2_2") (pintype "passive"))
      (node (ref "R12") (pin "1") (pinfunction "1_1") (pintype "passive"))
    )
    (net (code "48") (name "Net-(IC3-DR_C)") (class "Default")
      (node (ref "IC3") (pin "1") (pinfunction "SW_C_1") (pintype "bidirectional"))
      (node (ref "IC3") (pin "7") (pinfunction "SENS_7") (pintype "bidirectional"))
      (node (ref "IC3") (pin "8") (pinfunction "DR_C_8") (pintype "bidirectional"))
      (node (ref "R10") (pin "2") (pinfunction "2_2") (pintype "passive"))
    )
    (net (code "49") (name "Net-(IC3-SW_E)") (class "Default")
      (node (ref "D14") (pin "C") (pinfunction "C_C") (pintype "passive"))
      (node (ref "IC3") (pin "2") (pinfunction "SW_E_2") (pintype "bidirectional"))
      (node (ref "L2") (pin "2") (pinfunction "2_2") (pintype "passive"))
    )
    (net (code "50") (name "Net-(IC3-TC)") (class "Default")
      (node (ref "C5") (pin "2") (pinfunction "2_2") (pintype "passive"))
      (node (ref "IC3") (pin "3") (pinfunction "TC_3") (pintype "bidirectional"))
    )
    (net (code "51") (name "Net-(LED1-PadC)") (class "Default")
      (node (ref "LED1") (pin "C") (pinfunction "C_C") (pintype "passive"))
      (node (ref "R8") (pin "1") (pinfunction "1_1") (pintype "passive"))
    )
    (net (code "52") (name "Net-(LED2-PadC)") (class "Default")
      (node (ref "LED2") (pin "C") (pinfunction "C_C") (pintype "passive"))
      (node (ref "R7") (pin "1") (pinfunction "1_1") (pintype "passive"))
    )
    (net (code "53") (name "Net-(LED3-PadA)") (class "Default")
      (node (ref "LED3") (pin "A") (pinfunction "A_A") (pintype "passive"))
      (node (ref "R3") (pin "2") (pinfunction "2_2") (pintype "passive"))
    )
    (net (code "54") (name "Net-(LED4-PadA)") (class "Default")
      (node (ref "LED4") (pin "A") (pinfunction "A_A") (pintype "passive"))
      (node (ref "R14") (pin "2") (pinfunction "2_2") (pintype "passive"))
    )
    (net (code "55") (name "Net-(LED5-PadA)") (class "Default")
      (node (ref "LED5") (pin "A") (pinfunction "A_A") (pintype "passive"))
      (node (ref "R16") (pin "2") (pinfunction "2_2") (pintype "passive"))
    )
    (net (code "56") (name "Net-(LED6-PadA)") (class "Default")
      (node (ref "LED6") (pin "A") (pinfunction "A_A") (pintype "passive"))
      (node (ref "R18") (pin "2") (pinfunction "2_2") (pintype "passive"))
    )
    (net (code "57") (name "Net-(LED7-PadA)") (class "Default")
      (node (ref "LED7") (pin "A") (pinfunction "A_A") (pintype "passive"))
      (node (ref "R20") (pin "2") (pinfunction "2_2") (pintype "passive"))
    )
    (net (code "58") (name "Net-(LED8-PadA)") (class "Default")
      (node (ref "LED8") (pin "A") (pinfunction "A_A") (pintype "passive"))
      (node (ref "R22") (pin "2") (pinfunction "2_2") (pintype "passive"))
    )
    (net (code "59") (name "Net-(LED9-PadA)") (class "Default")
      (node (ref "LED9") (pin "A") (pinfunction "A_A") (pintype "passive"))
      (node (ref "R24") (pin "2") (pinfunction "2_2") (pintype "passive"))
    )
    (net (code "60") (name "Net-(LED10-PadA)") (class "Default")
      (node (ref "LED10") (pin "A") (pinfunction "A_A") (pintype "passive"))
      (node (ref "R9") (pin "2") (pinfunction "2_2") (pintype "passive"))
    )
    (net (code "61") (name "Net-(MIDI_IN-Pad4)") (class "Default")
      (node (ref "MIDI_IN") (pin "4") (pinfunction "4_4") (pintype "passive"))
      (node (ref "R1") (pin "2") (pinfunction "2_2") (pintype "passive"))
    )
    (net (code "62") (name "Net-(R2-Pad1)") (class "Default")
      (node (ref "R2") (pin "1") (pinfunction "1_1") (pintype "passive"))
      (node (ref "TR2") (pin "B") (pinfunction "B_B") (pintype "passive"))
    )
    (net (code "63") (name "Net-(R6-Pad2)") (class "Default")
      (node (ref "R6") (pin "2") (pinfunction "2_2") (pintype "passive"))
      (node (ref "TR1") (pin "B") (pinfunction "B_B") (pintype "passive"))
    )
    (net (code "64") (name "Net-(R13-Pad1)") (class "Default")
      (node (ref "R13") (pin "1") (pinfunction "1_1") (pintype "passive"))
      (node (ref "TR3") (pin "B") (pinfunction "B_B") (pintype "passive"))
    )
    (net (code "65") (name "Net-(R15-Pad1)") (class "Default")
      (node (ref "R15") (pin "1") (pinfunction "1_1") (pintype "passive"))
      (node (ref "TR4") (pin "B") (pinfunction "B_B") (pintype "passive"))
    )
    (net (code "66") (name "Net-(R17-Pad1)") (class "Default")
      (node (ref "R17") (pin "1") (pinfunction "1_1") (pintype "passive"))
      (node (ref "TR5") (pin "B") (pinfunction "B_B") (pintype "passive"))
    )
    (net (code "67") (name "Net-(R19-Pad1)") (class "Default")
      (node (ref "R19") (pin "1") (pinfunction "1_1") (pintype "passive"))
      (node (ref "TR6") (pin "B") (pinfunction "B_B") (pintype "passive"))
    )
    (net (code "68") (name "Net-(R21-Pad1)") (class "Default")
      (node (ref "R21") (pin "1") (pinfunction "1_1") (pintype "passive"))
      (node (ref "TR7") (pin "B") (pinfunction "B_B") (pintype "passive"))
    )
    (net (code "69") (name "Net-(R23-Pad1)") (class "Default")
      (node (ref "R23") (pin "1") (pinfunction "1_1") (pintype "passive"))
      (node (ref "TR8") (pin "B") (pinfunction "B_B") (pintype "passive"))
    )
    (net (code "70") (name "Net-(R25-Pad1)") (class "Default")
      (node (ref "R25") (pin "1") (pinfunction "1_1") (pintype "passive"))
      (node (ref "TR9") (pin "B") (pinfunction "B_B") (pintype "passive"))
    )
    (net (code "71") (name "unconnected-(ICSP-Pad6)") (class "Default")
      (node (ref "ICSP") (pin "6") (pinfunction "6_6") (pintype "passive"))
    )
    (net (code "72") (name "unconnected-(MIDI_IN-Pad1)") (class "Default")
      (node (ref "MIDI_IN") (pin "1") (pinfunction "1_1") (pintype "passive"))
    )
    (net (code "73") (name "unconnected-(MIDI_IN-Pad2)") (class "Default")
      (node (ref "MIDI_IN") (pin "2") (pinfunction "2_2") (pintype "passive"))
    )
    (net (code "74") (name "unconnected-(MIDI_IN-Pad3)") (class "Default")
      (node (ref "MIDI_IN") (pin "3") (pinfunction "3_3") (pintype "passive"))
    )
    (net (code "75") (name "unconnected-(U$1-PadRING_SW)") (class "Default")
      (node (ref "U$1") (pin "RING_SW") (pinfunction "RING_SW_RING_SW") (pintype "bidirectional"))
    )
  )
)
